# sensor.net
KiCad netlist of a schematic drawn in Altium Designer
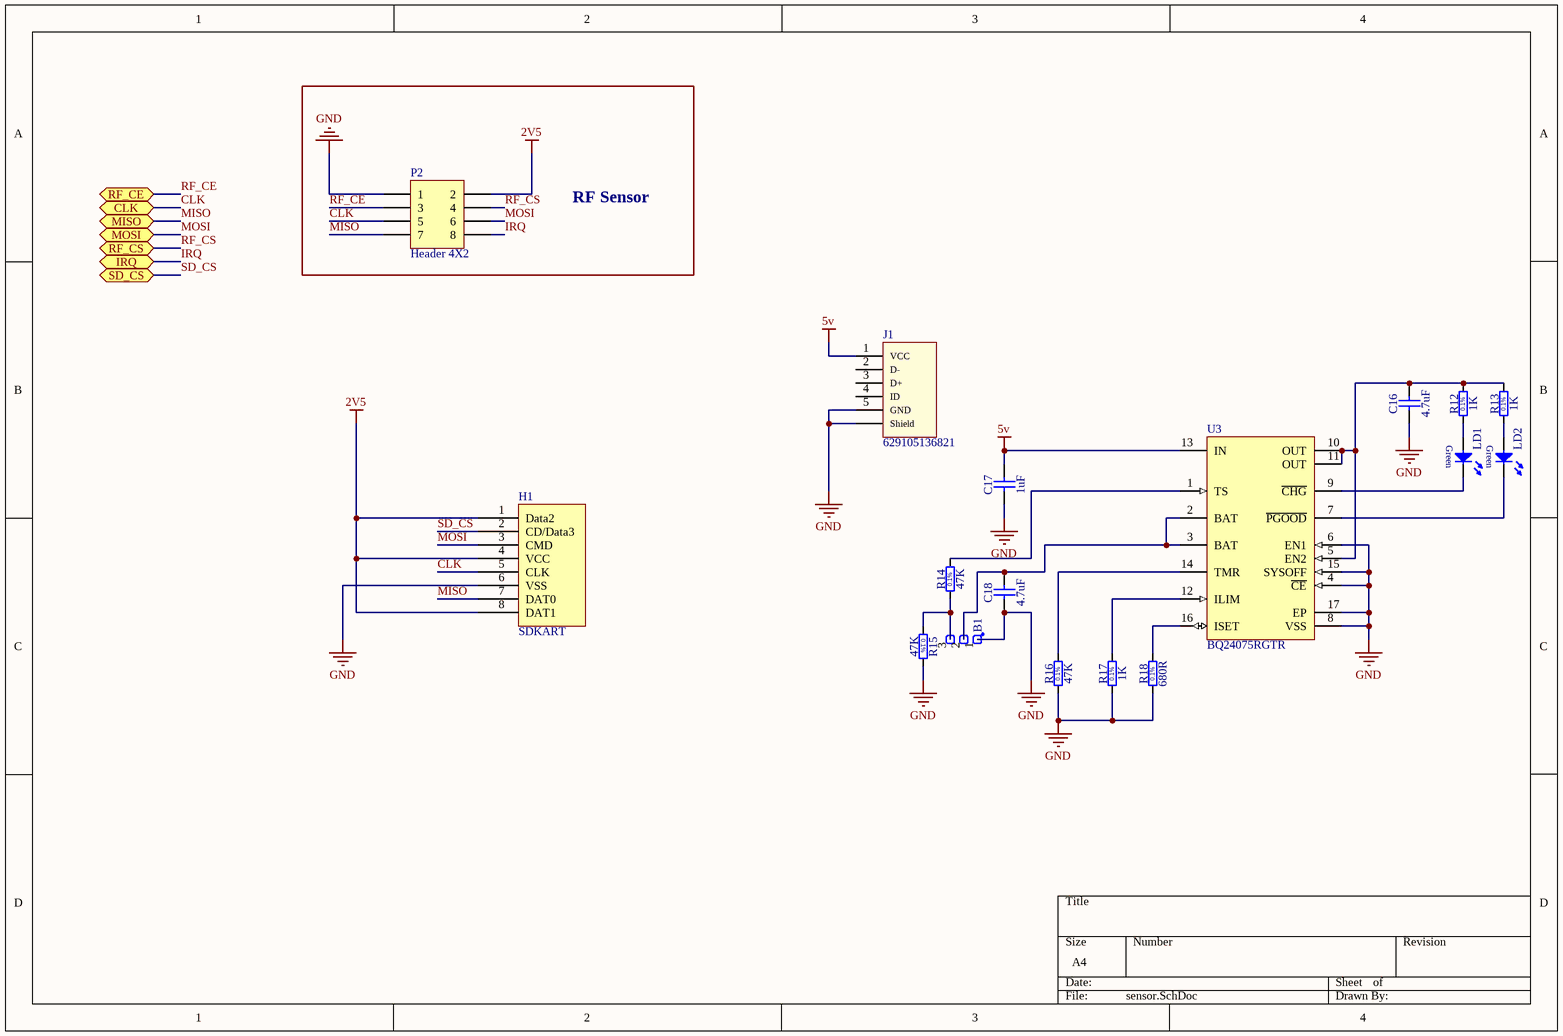
[diagram p0: sensor.SchDoc]

(export (version "E")
  (design (tool "Eeschema 10.0.6"))
  (components
    (comp (ref "B1")
      (value "Test Point")
      (footprint "COMATEL_331.0600.1.03.500")
      (description "3 Positions Terminal Strip")
      (fields
        (field (name "PART NUMBER") "COMATEL_331.0600.1.03.500")
        (field (name "MANUFACTURER") "KONTEK COMATEL")
        (field (name "AUTHOR") "CERN DEM JLC")
      )
      (libsource (lib "Connectors") (part "Terminal Strip 3 Positions"))
    )
    (comp (ref "C16")
      (value "4.7uF")
      (footprint "CAPC2012X135N")
      (description "Non-polarised capacitor")
      (fields
        (field (name "PART NUMBER") "CC0805_10NF_50V_10%_X7R")
        (field (name "VOLTAGE") "50V")
        (field (name "AUTHOR") "CERN DEM JLC")
      )
      (libsource (lib "Capacitors") (part "Capacitor - non polarized"))
    )
    (comp (ref "C17")
      (value "1uF")
      (footprint "CAPC2012X135N")
      (description "Non-polarised capacitor")
      (fields
        (field (name "PART NUMBER") "CC0805_10NF_50V_10%_X7R")
        (field (name "VOLTAGE") "50V")
        (field (name "AUTHOR") "CERN DEM JLC")
      )
      (libsource (lib "Capacitors") (part "Capacitor - non polarized"))
    )
    (comp (ref "C18")
      (value "4.7uF")
      (footprint "CAPC2012X135N")
      (description "Non-polarised capacitor")
      (fields
        (field (name "PART NUMBER") "CC0805_10NF_50V_10%_X7R")
        (field (name "VOLTAGE") "50V")
        (field (name "AUTHOR") "CERN DEM JLC")
      )
      (libsource (lib "Capacitors") (part "Capacitor - non polarized"))
    )
    (comp (ref "H1")
      (value "SDKART")
      (footprint "PCBComponent_1")
      (libsource (lib "Integrated_Library") (part "SDKART"))
    )
    (comp (ref "J1")
      (value "629105136821")
      (footprint "629105136821")
      (description "Micro USB 2.0 SMT Type B Horizontal 5 Contacts WR-COM")
      (fields (field (name "PUBLISHER") "Wurth Elektronik"))
      (libsource (lib "Altium_WR-COM (rev17a)") (part "629105136821"))
    )
    (comp (ref "LD1")
      (value "Green")
      (footprint "LED_OSRAM_LGR971")
      (description "LED Green 1C 2A")
      (fields
        (field (name "PART NUMBER") "LED_OSRAM_LGR971")
        (field (name "MANUFACTURER") "OSRAM")
        (field (name "AUTHOR") "CERN DEM JLC")
      )
      (libsource (lib "ICs And Semiconductors") (part "LED Green 1C 2A"))
    )
    (comp (ref "LD2")
      (value "Green")
      (footprint "LED_OSRAM_LGR971")
      (description "LED Green 1C 2A")
      (fields
        (field (name "PART NUMBER") "LED_OSRAM_LGR971")
        (field (name "MANUFACTURER") "OSRAM")
        (field (name "AUTHOR") "CERN DEM JLC")
      )
      (libsource (lib "ICs And Semiconductors") (part "LED Green 1C 2A"))
    )
    (comp (ref "P2")
      (value "Header 4X2")
      (footprint "HDR2X4")
      (description "Header, 4-Pin, Dual row")
      (fields (field (name "PUBLISHER") "Altium Limited"))
      (libsource (lib "Miscellaneous Connectors") (part "Header 4X2"))
    )
    (comp (ref "R12")
      (value "1K")
      (footprint "RESC2012X60N")
      (description "Resistor - 0.1%")
      (fields
        (field (name "PART NUMBER") "R0805_1K1_0.1%_0.1W_10PPM")
        (field (name "POWER") "0.1W")
        (field (name "AUTHOR") "CERN DEM JLC")
      )
      (libsource (lib "Resistors") (part "Resistor - 0.1%"))
    )
    (comp (ref "R13")
      (value "1K")
      (footprint "RESC2012X60N")
      (description "Resistor - 0.1%")
      (fields
        (field (name "PART NUMBER") "R0805_1K1_0.1%_0.1W_10PPM")
        (field (name "POWER") "0.1W")
        (field (name "AUTHOR") "CERN DEM JLC")
      )
      (libsource (lib "Resistors") (part "Resistor - 0.1%"))
    )
    (comp (ref "R14")
      (value "47K")
      (footprint "RESC2012X60N")
      (description "Resistor - 0.1%")
      (fields
        (field (name "PART NUMBER") "R0805_1K1_0.1%_0.1W_10PPM")
        (field (name "POWER") "0.1W")
        (field (name "AUTHOR") "CERN DEM JLC")
      )
      (libsource (lib "Resistors") (part "Resistor - 0.1%"))
    )
    (comp (ref "R15")
      (value "47K")
      (footprint "RESC2012X60N")
      (description "Resistor - 0.1%")
      (fields
        (field (name "PART NUMBER") "R0805_1K1_0.1%_0.1W_10PPM")
        (field (name "POWER") "0.1W")
        (field (name "AUTHOR") "CERN DEM JLC")
      )
      (libsource (lib "Resistors") (part "Resistor - 0.1%"))
    )
    (comp (ref "R16")
      (value "47K")
      (footprint "RESC2012X60N")
      (description "Resistor - 0.1%")
      (fields
        (field (name "PART NUMBER") "R0805_1K1_0.1%_0.1W_10PPM")
        (field (name "POWER") "0.1W")
        (field (name "AUTHOR") "CERN DEM JLC")
      )
      (libsource (lib "Resistors") (part "Resistor - 0.1%"))
    )
    (comp (ref "R17")
      (value "1K")
      (footprint "RESC2012X60N")
      (description "Resistor - 0.1%")
      (fields
        (field (name "PART NUMBER") "R0805_1K1_0.1%_0.1W_10PPM")
        (field (name "POWER") "0.1W")
        (field (name "AUTHOR") "CERN DEM JLC")
      )
      (libsource (lib "Resistors") (part "Resistor - 0.1%"))
    )
    (comp (ref "R18")
      (value "680R")
      (footprint "RESC2012X60N")
      (description "Resistor - 0.1%")
      (fields
        (field (name "PART NUMBER") "R0805_1K1_0.1%_0.1W_10PPM")
        (field (name "POWER") "0.1W")
        (field (name "AUTHOR") "CERN DEM JLC")
      )
      (libsource (lib "Resistors") (part "Resistor - 0.1%"))
    )
    (comp (ref "U3")
      (value "BQ24075RGTR")
      (footprint "RGT16-1700X1700TP")
      (fields (field (name "MANUFACTURER") "Texas Instruments"))
      (libsource (lib "TI Power Management Battery Management") (part "BQ24075RGTR"))
    )
  )
  (nets
    (net (code "1") (name "/CLK") (class "Default")
      (node (ref "H1") (pin "5") (pinfunction "CLK_5") (pintype "passive"))
      (node (ref "P2") (pin "5") (pinfunction "5_5") (pintype "passive"))
    )
    (net (code "2") (name "/IRQ") (class "Default")
      (node (ref "P2") (pin "8") (pinfunction "8_8") (pintype "passive"))
    )
    (net (code "3") (name "/MISO") (class "Default")
      (node (ref "H1") (pin "7") (pinfunction "DAT0_7") (pintype "passive"))
      (node (ref "P2") (pin "7") (pinfunction "7_7") (pintype "passive"))
    )
    (net (code "4") (name "/MOSI") (class "Default")
      (node (ref "H1") (pin "3") (pinfunction "CMD_3") (pintype "passive"))
      (node (ref "P2") (pin "6") (pinfunction "6_6") (pintype "passive"))
    )
    (net (code "5") (name "/RF_CE") (class "Default")
      (node (ref "P2") (pin "3") (pinfunction "3_3") (pintype "passive"))
    )
    (net (code "6") (name "/RF_CS") (class "Default")
      (node (ref "P2") (pin "4") (pinfunction "4_4") (pintype "passive"))
    )
    (net (code "7") (name "/SD_CS") (class "Default")
      (node (ref "H1") (pin "2") (pinfunction "CD/Data3_2") (pintype "passive"))
    )
    (net (code "8") (name "2V5") (class "Default")
      (node (ref "H1") (pin "1") (pinfunction "Data2_1") (pintype "passive"))
      (node (ref "H1") (pin "4") (pinfunction "VCC_4") (pintype "passive"))
      (node (ref "H1") (pin "8") (pinfunction "DAT1_8") (pintype "passive"))
      (node (ref "P2") (pin "2") (pinfunction "2_2") (pintype "passive"))
    )
    (net (code "9") (name "5v") (class "Default")
      (node (ref "C17") (pin "2") (pinfunction "2_2") (pintype "passive"))
      (node (ref "J1") (pin "1") (pinfunction "VCC_1") (pintype "passive"))
      (node (ref "U3") (pin "13") (pinfunction "IN_13") (pintype "power_in"))
    )
    (net (code "10") (name "GND") (class "Default")
      (node (ref "B1") (pin "1") (pinfunction "1_1") (pintype "bidirectional"))
      (node (ref "C16") (pin "1") (pinfunction "1_1") (pintype "passive"))
      (node (ref "C17") (pin "1") (pinfunction "1_1") (pintype "passive"))
      (node (ref "C18") (pin "1") (pinfunction "1_1") (pintype "passive"))
      (node (ref "H1") (pin "6") (pinfunction "VSS_6") (pintype "passive"))
      (node (ref "J1") (pin "5") (pinfunction "GND_5") (pintype "passive"))
      (node (ref "J1") (pin "Shell") (pinfunction "Shield_Shell") (pintype "passive"))
      (node (ref "P2") (pin "1") (pinfunction "1_1") (pintype "passive"))
      (node (ref "R15") (pin "2") (pinfunction "2_2") (pintype "passive"))
      (node (ref "R16") (pin "1") (pinfunction "1_1") (pintype "passive"))
      (node (ref "R17") (pin "1") (pinfunction "1_1") (pintype "passive"))
      (node (ref "R18") (pin "1") (pinfunction "1_1") (pintype "passive"))
      (node (ref "U3") (pin "15") (pinfunction "SYSOFF_15") (pintype "input"))
      (node (ref "U3") (pin "17") (pinfunction "EP_17") (pintype "power_in"))
      (node (ref "U3") (pin "4") (pinfunction "~{CE}_4") (pintype "input"))
      (node (ref "U3") (pin "6") (pinfunction "EN1_6") (pintype "input"))
      (node (ref "U3") (pin "8") (pinfunction "VSS_8") (pintype "power_in"))
    )
    (net (code "11") (name "Net-(B1-Pad2)") (class "Default")
      (node (ref "B1") (pin "2") (pinfunction "2_2") (pintype "bidirectional"))
      (node (ref "C18") (pin "2") (pinfunction "2_2") (pintype "passive"))
      (node (ref "U3") (pin "2") (pinfunction "BAT_2") (pintype "power_in"))
      (node (ref "U3") (pin "3") (pinfunction "BAT_3") (pintype "power_in"))
    )
    (net (code "12") (name "Net-(B1-Pad3)") (class "Default")
      (node (ref "B1") (pin "3") (pinfunction "3_3") (pintype "bidirectional"))
      (node (ref "R14") (pin "1") (pinfunction "1_1") (pintype "passive"))
      (node (ref "R15") (pin "1") (pinfunction "1_1") (pintype "passive"))
    )
    (net (code "13") (name "Net-(LD1-A)") (class "Default")
      (node (ref "LD1") (pin "2") (pinfunction "A_2") (pintype "passive"))
      (node (ref "R12") (pin "1") (pinfunction "1_1") (pintype "passive"))
    )
    (net (code "14") (name "Net-(LD1-C)") (class "Default")
      (node (ref "LD1") (pin "1") (pinfunction "C_1") (pintype "passive"))
      (node (ref "U3") (pin "9") (pinfunction "~{CHG}_9") (pintype "tri_state"))
    )
    (net (code "15") (name "Net-(LD2-A)") (class "Default")
      (node (ref "LD2") (pin "2") (pinfunction "A_2") (pintype "passive"))
      (node (ref "R13") (pin "1") (pinfunction "1_1") (pintype "passive"))
    )
    (net (code "16") (name "Net-(LD2-C)") (class "Default")
      (node (ref "LD2") (pin "1") (pinfunction "C_1") (pintype "passive"))
      (node (ref "U3") (pin "7") (pinfunction "~{PGOOD}_7") (pintype "tri_state"))
    )
    (net (code "17") (name "Net-(U3-EN2)") (class "Default")
      (node (ref "C16") (pin "2") (pinfunction "2_2") (pintype "passive"))
      (node (ref "R12") (pin "2") (pinfunction "2_2") (pintype "passive"))
      (node (ref "R13") (pin "2") (pinfunction "2_2") (pintype "passive"))
      (node (ref "U3") (pin "10") (pinfunction "OUT_10") (pintype "power_in"))
      (node (ref "U3") (pin "11") (pinfunction "OUT_11") (pintype "power_in"))
      (node (ref "U3") (pin "5") (pinfunction "EN2_5") (pintype "input"))
    )
    (net (code "18") (name "Net-(U3-ILIM)") (class "Default")
      (node (ref "R17") (pin "2") (pinfunction "2_2") (pintype "passive"))
      (node (ref "U3") (pin "12") (pinfunction "ILIM_12") (pintype "input"))
    )
    (net (code "19") (name "Net-(U3-ISET)") (class "Default")
      (node (ref "R18") (pin "2") (pinfunction "2_2") (pintype "passive"))
      (node (ref "U3") (pin "16") (pinfunction "ISET_16") (pintype "bidirectional"))
    )
    (net (code "20") (name "Net-(U3-TMR)") (class "Default")
      (node (ref "R16") (pin "2") (pinfunction "2_2") (pintype "passive"))
      (node (ref "U3") (pin "14") (pinfunction "TMR_14") (pintype "passive"))
    )
    (net (code "21") (name "Net-(U3-TS)") (class "Default")
      (node (ref "R14") (pin "2") (pinfunction "2_2") (pintype "passive"))
      (node (ref "U3") (pin "1") (pinfunction "TS_1") (pintype "input"))
    )
    (net (code "22") (name "unconnected-(J1-D+-Pad3)") (class "Default")
      (node (ref "J1") (pin "3") (pinfunction "D+_3") (pintype "passive"))
    )
    (net (code "23") (name "unconnected-(J1-D--Pad2)") (class "Default")
      (node (ref "J1") (pin "2") (pinfunction "D-_2") (pintype "passive"))
    )
    (net (code "24") (name "unconnected-(J1-ID-Pad4)") (class "Default")
      (node (ref "J1") (pin "4") (pinfunction "ID_4") (pintype "passive"))
    )
  )
)
